# Debug.net
KiCad netlist of a schematic drawn in Altium Designer
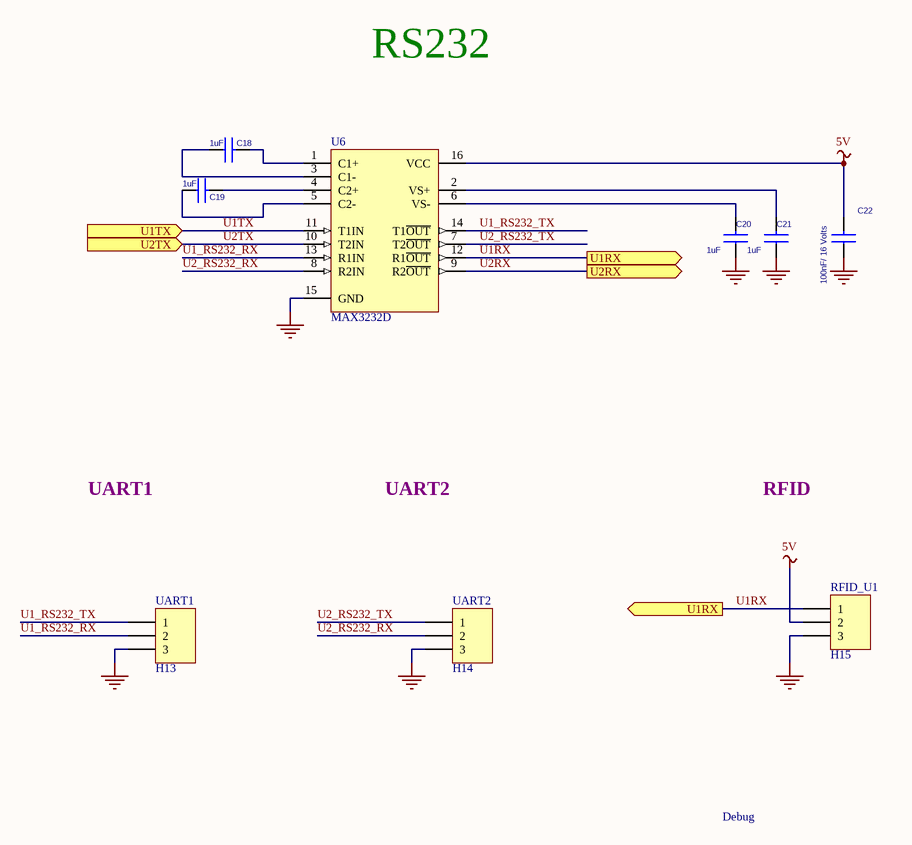
[diagram p0: Debug.SchDoc]

(export (version "E")
  (design (tool "Eeschema 10.0.6"))
  (components
    (comp (ref "C18")
      (value "1uF")
      (footprint "CAP_CERAMIC")
      (libsource (lib "combined_cart_schematic_lib") (part "CAP NP"))
    )
    (comp (ref "C19")
      (value "1uF")
      (footprint "CAP_CERAMIC")
      (libsource (lib "combined_cart_schematic_lib") (part "CAP NP"))
    )
    (comp (ref "C20")
      (value "1uF")
      (footprint "CAP_CERAMIC")
      (libsource (lib "combined_cart_schematic_lib") (part "CAP NP"))
    )
    (comp (ref "C21")
      (value "1uF")
      (footprint "CAP_CERAMIC")
      (libsource (lib "combined_cart_schematic_lib") (part "CAP NP"))
    )
    (comp (ref "C22")
      (value "100nF/ 16 Volts")
      (footprint "CAP_CERAMIC")
      (libsource (lib "combined_cart_schematic_lib") (part "CAP NP"))
    )
    (comp (ref "RFID_U1")
      (value "H15")
      (footprint "1x3_single - duplicate")
      (description "Header, 3-Pin")
      (fields (field (name "PUBLISHER") "Altium Limited"))
      (libsource (lib "combined_cart_schematic_lib") (part "Header 3"))
    )
    (comp (ref "U6")
      (value "MAX3232D")
      (footprint "MAX232D")
      (description "Dual EIA-232 Driver/Receiver")
      (fields (field (name "PUBLISHER") "Altium Limited"))
      (libsource (lib "combined_cart_schematic_lib") (part "MAX232D"))
    )
    (comp (ref "UART1")
      (value "H13")
      (footprint "1x3_single - duplicate")
      (description "Header, 3-Pin")
      (fields (field (name "PUBLISHER") "Altium Limited"))
      (libsource (lib "combined_cart_schematic_lib") (part "Header 3"))
    )
    (comp (ref "UART2")
      (value "H14")
      (footprint "1x3_single - duplicate")
      (description "Header, 3-Pin")
      (fields (field (name "PUBLISHER") "Altium Limited"))
      (libsource (lib "combined_cart_schematic_lib") (part "Header 3"))
    )
  )
  (nets
    (net (code "1") (name "/U1RX") (class "Default")
      (node (ref "RFID_U1") (pin "1") (pinfunction "1_1") (pintype "passive"))
      (node (ref "U6") (pin "12") (pinfunction "R1~{OUT}_12") (pintype "output"))
    )
    (net (code "2") (name "/U1TX") (class "Default")
      (node (ref "U6") (pin "11") (pinfunction "T1IN_11") (pintype "input"))
    )
    (net (code "3") (name "/U1_RS232_RX") (class "Default")
      (node (ref "U6") (pin "13") (pinfunction "R1IN_13") (pintype "input"))
      (node (ref "UART1") (pin "2") (pinfunction "2_2") (pintype "passive"))
    )
    (net (code "4") (name "/U1_RS232_TX") (class "Default")
      (node (ref "U6") (pin "14") (pinfunction "T1~{OUT}_14") (pintype "output"))
      (node (ref "UART1") (pin "1") (pinfunction "1_1") (pintype "passive"))
    )
    (net (code "5") (name "/U2RX") (class "Default")
      (node (ref "U6") (pin "9") (pinfunction "R2~{OUT}_9") (pintype "output"))
    )
    (net (code "6") (name "/U2TX") (class "Default")
      (node (ref "U6") (pin "10") (pinfunction "T2IN_10") (pintype "input"))
    )
    (net (code "7") (name "/U2_RS232_RX") (class "Default")
      (node (ref "U6") (pin "8") (pinfunction "R2IN_8") (pintype "input"))
      (node (ref "UART2") (pin "2") (pinfunction "2_2") (pintype "passive"))
    )
    (net (code "8") (name "/U2_RS232_TX") (class "Default")
      (node (ref "U6") (pin "7") (pinfunction "T2~{OUT}_7") (pintype "output"))
      (node (ref "UART2") (pin "1") (pinfunction "1_1") (pintype "passive"))
    )
    (net (code "9") (name "5V") (class "Default")
      (node (ref "C22") (pin "2") (pinfunction "2_2") (pintype "passive"))
      (node (ref "RFID_U1") (pin "2") (pinfunction "2_2") (pintype "passive"))
      (node (ref "U6") (pin "16") (pinfunction "VCC_16") (pintype "power_in"))
    )
    (net (code "10") (name "GND_POWER") (class "Default")
      (node (ref "C20") (pin "1") (pinfunction "1_1") (pintype "passive"))
      (node (ref "C21") (pin "1") (pinfunction "1_1") (pintype "passive"))
      (node (ref "C22") (pin "1") (pinfunction "1_1") (pintype "passive"))
      (node (ref "RFID_U1") (pin "3") (pinfunction "3_3") (pintype "passive"))
      (node (ref "U6") (pin "15") (pinfunction "GND_15") (pintype "power_in"))
      (node (ref "UART1") (pin "3") (pinfunction "3_3") (pintype "passive"))
      (node (ref "UART2") (pin "3") (pinfunction "3_3") (pintype "passive"))
    )
    (net (code "11") (name "Net-(U6-C1+)") (class "Default")
      (node (ref "C18") (pin "2") (pinfunction "2_2") (pintype "passive"))
      (node (ref "U6") (pin "1") (pinfunction "C1+_1") (pintype "passive"))
    )
    (net (code "12") (name "Net-(U6-C1-)") (class "Default")
      (node (ref "C18") (pin "1") (pinfunction "1_1") (pintype "passive"))
      (node (ref "U6") (pin "3") (pinfunction "C1-_3") (pintype "passive"))
    )
    (net (code "13") (name "Net-(U6-C2+)") (class "Default")
      (node (ref "C19") (pin "2") (pinfunction "2_2") (pintype "passive"))
      (node (ref "U6") (pin "4") (pinfunction "C2+_4") (pintype "passive"))
    )
    (net (code "14") (name "Net-(U6-C2-)") (class "Default")
      (node (ref "C19") (pin "1") (pinfunction "1_1") (pintype "passive"))
      (node (ref "U6") (pin "5") (pinfunction "C2-_5") (pintype "passive"))
    )
    (net (code "15") (name "Net-(U6-VS+)") (class "Default")
      (node (ref "C21") (pin "2") (pinfunction "2_2") (pintype "passive"))
      (node (ref "U6") (pin "2") (pinfunction "VS+_2") (pintype "power_in"))
    )
    (net (code "16") (name "Net-(U6-VS-)") (class "Default")
      (node (ref "C20") (pin "2") (pinfunction "2_2") (pintype "passive"))
      (node (ref "U6") (pin "6") (pinfunction "VS-_6") (pintype "power_in"))
    )
  )
)
